# CH32V006K8U6-R0-1v0.net
KiCad netlist of a schematic drawn in Altium Designer
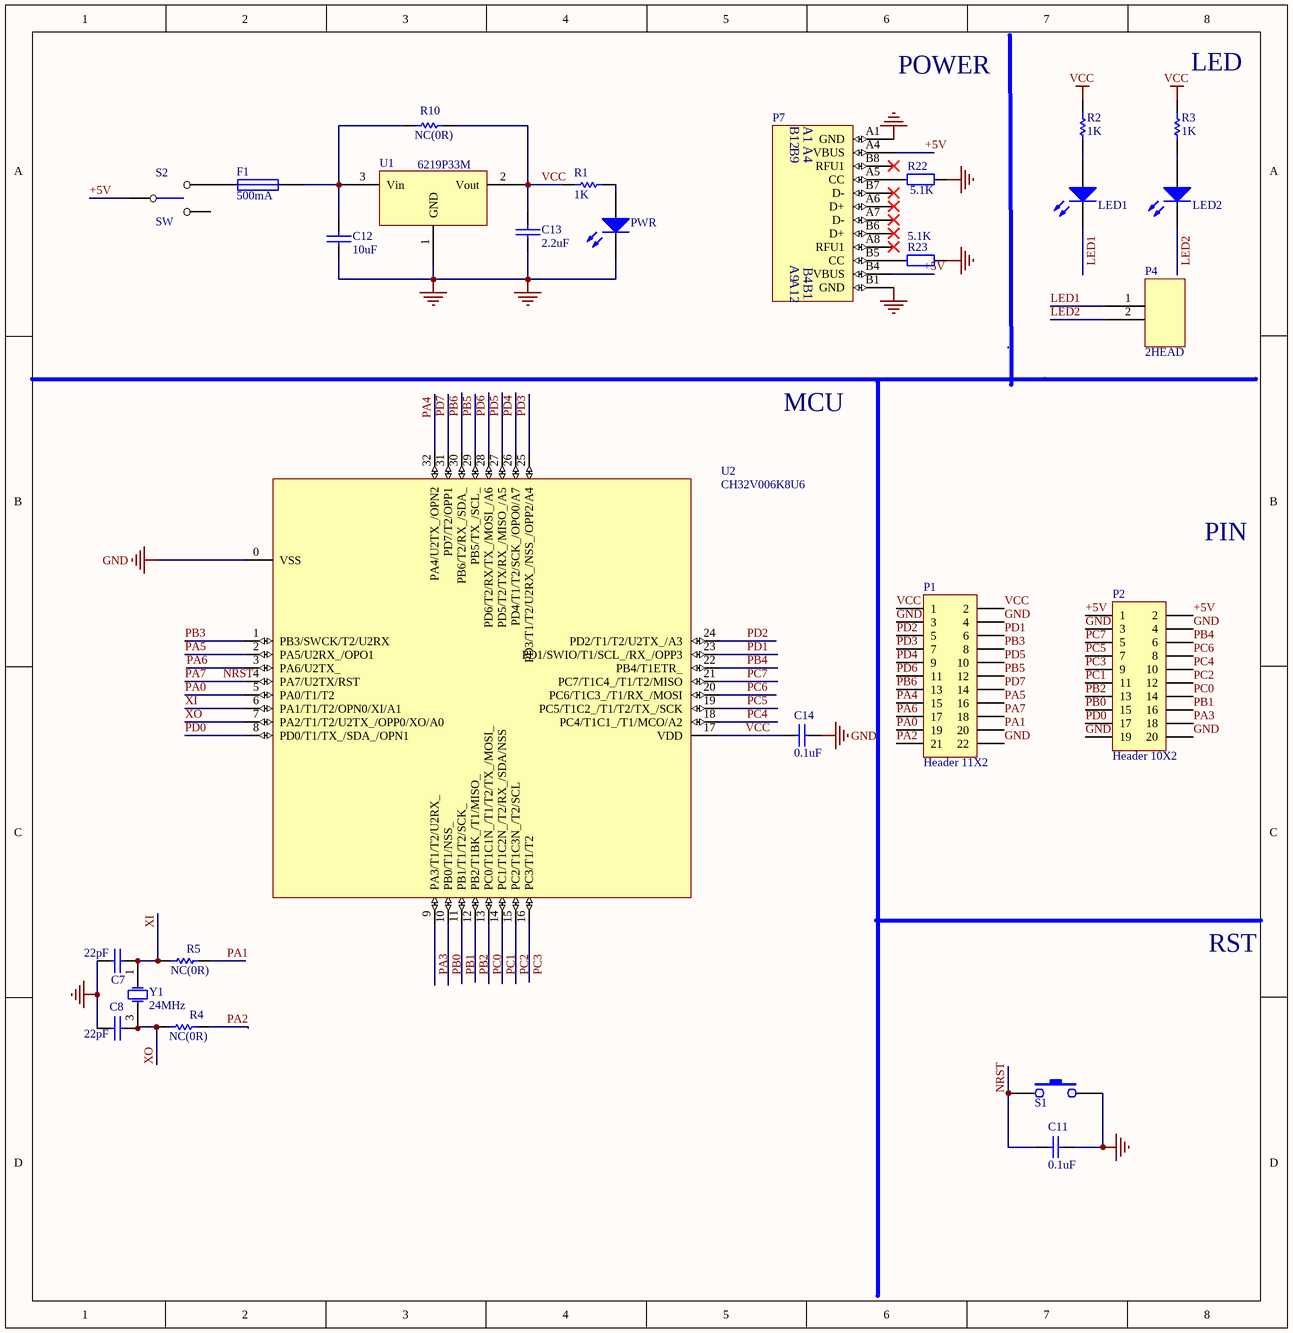
[diagram p0: CH32V006K8U6-R0-1v0.SchDoc]

(export (version "E")
  (design (tool "Eeschema 10.0.6"))
  (components
    (comp (ref "C7")
      (value "22pF")
      (footprint "0402_C")
      (description "Capacitor")
      (libsource (lib "*") (part "CAP"))
    )
    (comp (ref "C8")
      (value "22pF")
      (footprint "0402_C")
      (description "Capacitor")
      (libsource (lib "*") (part "CAP"))
    )
    (comp (ref "C11")
      (value "0.1uF")
      (footprint "0402_C")
      (description "Capacitor")
      (fields (field (name "PUBLISHER") "Altium Limited"))
      (libsource (lib "*") (part "Cap"))
    )
    (comp (ref "C12")
      (value "10uF")
      (footprint "0603_C")
      (description "Capacitor")
      (libsource (lib "wch_sch_others") (part "CAP"))
    )
    (comp (ref "C13")
      (value "2.2uF")
      (footprint "0402_C")
      (description "Capacitor")
      (libsource (lib "wch_sch_others") (part "CAP"))
    )
    (comp (ref "C14")
      (value "0.1uF")
      (footprint "0402_C")
      (description "Capacitor")
      (fields (field (name "PUBLISHER") "Altium Limited"))
      (libsource (lib "*") (part "Cap"))
    )
    (comp (ref "F1")
      (value "500mA")
      (footprint "0603")
      (description "Fuse")
      (libsource (lib "*") (part "FUSE1"))
    )
    (comp (ref "LED1")
      (value "LED1   blue")
      (footprint "0603+")
      (description "Typical INFRARED GaAs LED")
      (fields (field (name "PUBLISHER") "Altium Limited"))
      (libsource (lib "*") (part "LED0"))
    )
    (comp (ref "LED2")
      (value "LED2  blue")
      (footprint "0603+")
      (description "Typical INFRARED GaAs LED")
      (fields (field (name "PUBLISHER") "Altium Limited"))
      (libsource (lib "*") (part "LED0"))
    )
    (comp (ref "P1")
      (value "Header 11X2")
      (footprint "IDC22-2.54mm")
      (description "Header, 11-Pin, Dual row")
      (fields (field (name "PUBLISHER") "Altium Limited"))
      (libsource (lib "Miscellaneous Connectors") (part "Header 11X2"))
    )
    (comp (ref "P2")
      (value "Header 10X2")
      (footprint "IDC20-2.54mm")
      (description "Header, 10-Pin, Dual row")
      (fields (field (name "PUBLISHER") "Altium Limited"))
      (libsource (lib "Miscellaneous Connectors") (part "Header 10X2"))
    )
    (comp (ref "P4") (value "2HEAD") (footprint "SIP2-2.54mm") (libsource (lib "*") (part "2HEAD")))
    (comp (ref "P7")
      (value "TYPE-C")
      (footprint "TYPE-C-Receptacle-2.0")
      (libsource (lib "*") (part "TYPE-C1"))
    )
    (comp (ref "PWR")
      (value "POWER  red")
      (footprint "0603+")
      (description "Typical INFRARED GaAs LED")
      (fields (field (name "PUBLISHER") "Altium Limited"))
      (libsource (lib "") (part "LED0_1"))
    )
    (comp (ref "R1")
      (value "1K")
      (footprint "0402")
      (description "Semiconductor Resistor")
      (fields (field (name "PUBLISHER") "Altium Limited"))
      (libsource (lib "*") (part "Res Semi"))
    )
    (comp (ref "R2")
      (value "1K")
      (footprint "0402")
      (description "Semiconductor Resistor")
      (fields (field (name "PUBLISHER") "Altium Limited"))
      (libsource (lib "*") (part "Res Semi"))
    )
    (comp (ref "R3")
      (value "1K")
      (footprint "0402")
      (description "Semiconductor Resistor")
      (fields (field (name "PUBLISHER") "Altium Limited"))
      (libsource (lib "*") (part "Res Semi"))
    )
    (comp (ref "R4")
      (value "NC(0R)")
      (footprint "0402")
      (description "Semiconductor Resistor")
      (fields (field (name "Comment") "0R") (field (name "PUBLISHER") "Altium Limited"))
      (libsource (lib "*") (part "Res Semi"))
    )
    (comp (ref "R5")
      (value "NC(0R)")
      (footprint "0402")
      (description "Semiconductor Resistor")
      (fields (field (name "Comment") "0R") (field (name "PUBLISHER") "Altium Limited"))
      (libsource (lib "*") (part "Res Semi"))
    )
    (comp (ref "R10")
      (value "NC(0R)")
      (footprint "0402")
      (description "Semiconductor Resistor")
      (fields (field (name "Comment") "0R") (field (name "PUBLISHER") "Altium Limited"))
      (libsource (lib "*") (part "Res Semi"))
    )
    (comp (ref "R22")
      (value "5.1K")
      (footprint "0402")
      (description "Resistor")
      (libsource (lib "Miscellaneous Devices") (part "Res2"))
    )
    (comp (ref "R23")
      (value "5.1K")
      (footprint "0402")
      (description "Resistor")
      (libsource (lib "Miscellaneous Devices") (part "Res2"))
    )
    (comp (ref "S1") (value "NRST") (footprint "SMD_6.1x3.65x2.5mm-KEY") (libsource (lib "*") (part "KEY")))
    (comp (ref "S2") (value "SW") (footprint "SW1") (libsource (lib "*") (part "SW")))
    (comp (ref "U1")
      (value "6219P33M")
      (footprint "SOT-23")
      (libsource (lib "wch_sch_others") (part "6219P33M"))
    )
    (comp (ref "U2")
      (value "CH32V006K8U6")
      (footprint "QFN32_4X4")
      (description "RISC-V MCU, 48MHz, ADC/OPA/2*UART/I2C/SPI")
      (libsource (lib "CHXXX(2)") (part "CH32V006K8U6"))
    )
    (comp (ref "Y1")
      (value "24MHz")
      (footprint "XT3225")
      (description "Crystal Oscillator")
      (fields (field (name "PUBLISHER") "Altium Limited"))
      (libsource (lib "*") (part "XTAL"))
    )
  )
  (nets
    (net (code "1") (name "/+5V") (class "Default")
      (node (ref "P2") (pin "1") (pinfunction "1_1") (pintype "passive"))
      (node (ref "P2") (pin "2") (pinfunction "2_2") (pintype "passive"))
      (node (ref "P7") (pin "A4") (pinfunction "VBUS_A4") (pintype "bidirectional"))
      (node (ref "P7") (pin "B4") (pinfunction "VBUS_B4") (pintype "bidirectional"))
      (node (ref "S2") (pin "1") (pinfunction "1_1") (pintype "passive"))
    )
    (net (code "2") (name "/LED1") (class "Default")
      (node (ref "LED1") (pin "2") (pinfunction "K_2") (pintype "passive"))
      (node (ref "P4") (pin "1") (pintype "passive"))
    )
    (net (code "3") (name "/LED2") (class "Default")
      (node (ref "LED2") (pin "2") (pinfunction "K_2") (pintype "passive"))
      (node (ref "P4") (pin "2") (pintype "passive"))
    )
    (net (code "4") (name "/NRST") (class "Default")
      (node (ref "C11") (pin "2") (pinfunction "2_2") (pintype "passive"))
      (node (ref "P1") (pin "18") (pinfunction "18_18") (pintype "passive"))
      (node (ref "S1") (pin "1") (pinfunction "1_1") (pintype "passive"))
      (node (ref "U2") (pin "4") (pinfunction "PA7/U2TX/RST_4") (pintype "bidirectional"))
    )
    (net (code "5") (name "/PA0") (class "Default")
      (node (ref "P1") (pin "19") (pinfunction "19_19") (pintype "passive"))
      (node (ref "U2") (pin "5") (pinfunction "PA0/T1/T2_5") (pintype "bidirectional"))
    )
    (net (code "6") (name "/PA1") (class "Default")
      (node (ref "P1") (pin "20") (pinfunction "20_20") (pintype "passive"))
      (node (ref "R5") (pin "2") (pinfunction "2_2") (pintype "passive"))
    )
    (net (code "7") (name "/PA2") (class "Default")
      (node (ref "P1") (pin "21") (pinfunction "21_21") (pintype "passive"))
      (node (ref "R4") (pin "2") (pinfunction "2_2") (pintype "passive"))
    )
    (net (code "8") (name "/PA3") (class "Default")
      (node (ref "P2") (pin "18") (pinfunction "18_18") (pintype "passive"))
      (node (ref "U2") (pin "9") (pinfunction "PA3/T1/T2/U2RX__9") (pintype "bidirectional"))
    )
    (net (code "9") (name "/PA4") (class "Default")
      (node (ref "P1") (pin "15") (pinfunction "15_15") (pintype "passive"))
      (node (ref "U2") (pin "32") (pinfunction "PA4/U2TX_/OPN2_32") (pintype "bidirectional"))
    )
    (net (code "10") (name "/PA5") (class "Default")
      (node (ref "P1") (pin "16") (pinfunction "16_16") (pintype "passive"))
      (node (ref "U2") (pin "2") (pinfunction "PA5/U2RX_/OPO1_2") (pintype "bidirectional"))
    )
    (net (code "11") (name "/PA6") (class "Default")
      (node (ref "P1") (pin "17") (pinfunction "17_17") (pintype "passive"))
      (node (ref "U2") (pin "3") (pinfunction "PA6/U2TX__3") (pintype "bidirectional"))
    )
    (net (code "12") (name "/PB0") (class "Default")
      (node (ref "P2") (pin "15") (pinfunction "15_15") (pintype "passive"))
      (node (ref "U2") (pin "10") (pinfunction "PB0/T1/NSS__10") (pintype "bidirectional"))
    )
    (net (code "13") (name "/PB1") (class "Default")
      (node (ref "P2") (pin "16") (pinfunction "16_16") (pintype "passive"))
      (node (ref "U2") (pin "11") (pinfunction "PB1/T1/T2/SCK__11") (pintype "bidirectional"))
    )
    (net (code "14") (name "/PB2") (class "Default")
      (node (ref "P2") (pin "13") (pinfunction "13_13") (pintype "passive"))
      (node (ref "U2") (pin "12") (pinfunction "PB2/T1BK_/T1/MISO__12") (pintype "bidirectional"))
    )
    (net (code "15") (name "/PB3") (class "Default")
      (node (ref "P1") (pin "8") (pinfunction "8_8") (pintype "passive"))
      (node (ref "U2") (pin "1") (pinfunction "PB3/SWCK/T2/U2RX_1") (pintype "bidirectional"))
    )
    (net (code "16") (name "/PB4") (class "Default")
      (node (ref "P2") (pin "6") (pinfunction "6_6") (pintype "passive"))
      (node (ref "U2") (pin "22") (pinfunction "PB4/T1ETR__22") (pintype "bidirectional"))
    )
    (net (code "17") (name "/PB5") (class "Default")
      (node (ref "P1") (pin "12") (pinfunction "12_12") (pintype "passive"))
      (node (ref "U2") (pin "29") (pinfunction "PB5/TX_/SCL__29") (pintype "bidirectional"))
    )
    (net (code "18") (name "/PB6") (class "Default")
      (node (ref "P1") (pin "13") (pinfunction "13_13") (pintype "passive"))
      (node (ref "U2") (pin "30") (pinfunction "PB6/T2/RX_/SDA__30") (pintype "bidirectional"))
    )
    (net (code "19") (name "/PC0") (class "Default")
      (node (ref "P2") (pin "14") (pinfunction "14_14") (pintype "passive"))
      (node (ref "U2") (pin "13") (pinfunction "PC0/T1C1N_/T1/T2/TX_/MOSI__13") (pintype "bidirectional"))
    )
    (net (code "20") (name "/PC1") (class "Default")
      (node (ref "P2") (pin "11") (pinfunction "11_11") (pintype "passive"))
      (node (ref "U2") (pin "14") (pinfunction "PC1/T1C2N_/T2/RX_/SDA/NSS_14") (pintype "bidirectional"))
    )
    (net (code "21") (name "/PC2") (class "Default")
      (node (ref "P2") (pin "12") (pinfunction "12_12") (pintype "passive"))
      (node (ref "U2") (pin "15") (pinfunction "PC2/T1C3N_/T2/SCL_15") (pintype "bidirectional"))
    )
    (net (code "22") (name "/PC3") (class "Default")
      (node (ref "P2") (pin "9") (pinfunction "9_9") (pintype "passive"))
      (node (ref "U2") (pin "16") (pinfunction "PC3/T1/T2_16") (pintype "bidirectional"))
    )
    (net (code "23") (name "/PC4") (class "Default")
      (node (ref "P2") (pin "10") (pinfunction "10_10") (pintype "passive"))
      (node (ref "U2") (pin "18") (pinfunction "PC4/T1C1_/T1/MCO/A2_18") (pintype "bidirectional"))
    )
    (net (code "24") (name "/PC5") (class "Default")
      (node (ref "P2") (pin "7") (pinfunction "7_7") (pintype "passive"))
      (node (ref "U2") (pin "19") (pinfunction "PC5/T1C2_/T1/T2/TX_/SCK_19") (pintype "bidirectional"))
    )
    (net (code "25") (name "/PC6") (class "Default")
      (node (ref "P2") (pin "8") (pinfunction "8_8") (pintype "passive"))
      (node (ref "U2") (pin "20") (pinfunction "PC6/T1C3_/T1/RX_/MOSI_20") (pintype "bidirectional"))
    )
    (net (code "26") (name "/PC7") (class "Default")
      (node (ref "P2") (pin "5") (pinfunction "5_5") (pintype "passive"))
      (node (ref "U2") (pin "21") (pinfunction "PC7/T1C4_/T1/T2/MISO_21") (pintype "bidirectional"))
    )
    (net (code "27") (name "/PD0") (class "Default")
      (node (ref "P2") (pin "17") (pinfunction "17_17") (pintype "passive"))
      (node (ref "U2") (pin "8") (pinfunction "PD0/T1/TX_/SDA_/OPN1_8") (pintype "bidirectional"))
    )
    (net (code "28") (name "/PD1") (class "Default")
      (node (ref "P1") (pin "6") (pinfunction "6_6") (pintype "passive"))
      (node (ref "U2") (pin "23") (pinfunction "PD1/SWIO/T1/SCL_/RX_/OPP3_23") (pintype "bidirectional"))
    )
    (net (code "29") (name "/PD2") (class "Default")
      (node (ref "P1") (pin "5") (pinfunction "5_5") (pintype "passive"))
      (node (ref "U2") (pin "24") (pinfunction "PD2/T1/T2/U2TX_/A3_24") (pintype "bidirectional"))
    )
    (net (code "30") (name "/PD3") (class "Default")
      (node (ref "P1") (pin "7") (pinfunction "7_7") (pintype "passive"))
      (node (ref "U2") (pin "25") (pinfunction "PD3/T1/T2/U2RX_/NSS_/OPP2/A4_25") (pintype "bidirectional"))
    )
    (net (code "31") (name "/PD4") (class "Default")
      (node (ref "P1") (pin "9") (pinfunction "9_9") (pintype "passive"))
      (node (ref "U2") (pin "26") (pinfunction "PD4/T1/T2/SCK_/OPO0/A7_26") (pintype "bidirectional"))
    )
    (net (code "32") (name "/PD5") (class "Default")
      (node (ref "P1") (pin "10") (pinfunction "10_10") (pintype "passive"))
      (node (ref "U2") (pin "27") (pinfunction "PD5/T2/TX/RX_/MISO_/A5_27") (pintype "bidirectional"))
    )
    (net (code "33") (name "/PD6") (class "Default")
      (node (ref "P1") (pin "11") (pinfunction "11_11") (pintype "passive"))
      (node (ref "U2") (pin "28") (pinfunction "PD6/T2/RX/TX_/MOSI_/A6_28") (pintype "bidirectional"))
    )
    (net (code "34") (name "/PD7") (class "Default")
      (node (ref "P1") (pin "14") (pinfunction "14_14") (pintype "passive"))
      (node (ref "U2") (pin "31") (pinfunction "PD7/T2/OPP1_31") (pintype "bidirectional"))
    )
    (net (code "35") (name "/XI") (class "Default")
      (node (ref "C7") (pin "2") (pinfunction "2_2") (pintype "passive"))
      (node (ref "R5") (pin "1") (pinfunction "1_1") (pintype "passive"))
      (node (ref "U2") (pin "6") (pinfunction "PA1/T1/T2/OPN0/XI/A1_6") (pintype "bidirectional"))
      (node (ref "Y1") (pin "1") (pinfunction "OSC1_1") (pintype "passive"))
    )
    (net (code "36") (name "/XO") (class "Default")
      (node (ref "C8") (pin "2") (pinfunction "2_2") (pintype "passive"))
      (node (ref "R4") (pin "1") (pinfunction "1_1") (pintype "passive"))
      (node (ref "U2") (pin "7") (pinfunction "PA2/T1/T2/U2TX_/OPP0/XO/A0_7") (pintype "bidirectional"))
      (node (ref "Y1") (pin "3") (pinfunction "OSC2_3") (pintype "passive"))
    )
    (net (code "37") (name "GND") (class "Default")
      (node (ref "C11") (pin "1") (pinfunction "1_1") (pintype "passive"))
      (node (ref "C12") (pin "2") (pinfunction "2_2") (pintype "passive"))
      (node (ref "C13") (pin "1") (pinfunction "1_1") (pintype "passive"))
      (node (ref "C14") (pin "2") (pinfunction "2_2") (pintype "passive"))
      (node (ref "C7") (pin "1") (pinfunction "1_1") (pintype "passive"))
      (node (ref "C8") (pin "1") (pinfunction "1_1") (pintype "passive"))
      (node (ref "P1") (pin "22") (pinfunction "22_22") (pintype "passive"))
      (node (ref "P1") (pin "3") (pinfunction "3_3") (pintype "passive"))
      (node (ref "P1") (pin "4") (pinfunction "4_4") (pintype "passive"))
      (node (ref "P2") (pin "19") (pinfunction "19_19") (pintype "passive"))
      (node (ref "P2") (pin "20") (pinfunction "20_20") (pintype "passive"))
      (node (ref "P2") (pin "3") (pinfunction "3_3") (pintype "passive"))
      (node (ref "P2") (pin "4") (pinfunction "4_4") (pintype "passive"))
      (node (ref "P7") (pin "A1") (pinfunction "GND_A1") (pintype "bidirectional"))
      (node (ref "P7") (pin "B1") (pinfunction "GND_B1") (pintype "bidirectional"))
      (node (ref "PWR") (pin "2") (pinfunction "K_2") (pintype "passive"))
      (node (ref "R22") (pin "2") (pinfunction "2_2") (pintype "passive"))
      (node (ref "R23") (pin "2") (pinfunction "2_2") (pintype "passive"))
      (node (ref "S1") (pin "2") (pinfunction "2_2") (pintype "passive"))
      (node (ref "U1") (pin "1") (pinfunction "GND_1") (pintype "passive"))
      (node (ref "U2") (pin "0") (pinfunction "VSS_0") (pintype "power_in"))
    )
    (net (code "38") (name "Net-(F1-Pad1)") (class "Default")
      (node (ref "F1") (pin "1") (pinfunction "1_1") (pintype "passive"))
      (node (ref "S2") (pin "3") (pinfunction "3_3") (pintype "passive"))
    )
    (net (code "39") (name "Net-(LED1-A)") (class "Default")
      (node (ref "LED1") (pin "1") (pinfunction "A_1") (pintype "passive"))
      (node (ref "R2") (pin "2") (pinfunction "2_2") (pintype "passive"))
    )
    (net (code "40") (name "Net-(LED2-A)") (class "Default")
      (node (ref "LED2") (pin "1") (pinfunction "A_1") (pintype "passive"))
      (node (ref "R3") (pin "2") (pinfunction "2_2") (pintype "passive"))
    )
    (net (code "41") (name "Net-(P7-CC-PadA5)") (class "Default")
      (node (ref "P7") (pin "A5") (pinfunction "CC_A5") (pintype "bidirectional"))
      (node (ref "R22") (pin "1") (pinfunction "1_1") (pintype "passive"))
    )
    (net (code "42") (name "Net-(P7-CC-PadB5)") (class "Default")
      (node (ref "P7") (pin "B5") (pinfunction "CC_B5") (pintype "bidirectional"))
      (node (ref "R23") (pin "1") (pinfunction "1_1") (pintype "passive"))
    )
    (net (code "43") (name "Net-(PWR-A)") (class "Default")
      (node (ref "PWR") (pin "1") (pinfunction "A_1") (pintype "passive"))
      (node (ref "R1") (pin "1") (pinfunction "1_1") (pintype "passive"))
    )
    (net (code "44") (name "Net-(U1-Vin)") (class "Default")
      (node (ref "C12") (pin "1") (pinfunction "1_1") (pintype "passive"))
      (node (ref "F1") (pin "2") (pinfunction "2_2") (pintype "passive"))
      (node (ref "R10") (pin "1") (pinfunction "1_1") (pintype "passive"))
      (node (ref "U1") (pin "3") (pinfunction "Vin_3") (pintype "passive"))
    )
    (net (code "45") (name "VCC") (class "Default")
      (node (ref "C13") (pin "2") (pinfunction "2_2") (pintype "passive"))
      (node (ref "C14") (pin "1") (pinfunction "1_1") (pintype "passive"))
      (node (ref "P1") (pin "1") (pinfunction "1_1") (pintype "passive"))
      (node (ref "P1") (pin "2") (pinfunction "2_2") (pintype "passive"))
      (node (ref "R1") (pin "2") (pinfunction "2_2") (pintype "passive"))
      (node (ref "R10") (pin "2") (pinfunction "2_2") (pintype "passive"))
      (node (ref "R2") (pin "1") (pinfunction "1_1") (pintype "passive"))
      (node (ref "R3") (pin "1") (pinfunction "1_1") (pintype "passive"))
      (node (ref "U1") (pin "2") (pinfunction "Vout_2") (pintype "passive"))
      (node (ref "U2") (pin "17") (pinfunction "VDD_17") (pintype "power_in"))
    )
    (net (code "46") (name "unconnected-(P7-D+-PadA6)") (class "Default")
      (node (ref "P7") (pin "A6") (pinfunction "D+_A6") (pintype "bidirectional+no_connect"))
    )
    (net (code "47") (name "unconnected-(P7-D+-PadB6)") (class "Default")
      (node (ref "P7") (pin "B6") (pinfunction "D+_B6") (pintype "bidirectional+no_connect"))
    )
    (net (code "48") (name "unconnected-(P7-D--PadA7)") (class "Default")
      (node (ref "P7") (pin "A7") (pinfunction "D-_A7") (pintype "bidirectional+no_connect"))
    )
    (net (code "49") (name "unconnected-(P7-D--PadB7)") (class "Default")
      (node (ref "P7") (pin "B7") (pinfunction "D-_B7") (pintype "bidirectional+no_connect"))
    )
    (net (code "50") (name "unconnected-(P7-RFU1-PadA8)") (class "Default")
      (node (ref "P7") (pin "A8") (pinfunction "RFU1_A8") (pintype "bidirectional+no_connect"))
    )
    (net (code "51") (name "unconnected-(P7-RFU1-PadB8)") (class "Default")
      (node (ref "P7") (pin "B8") (pinfunction "RFU1_B8") (pintype "bidirectional+no_connect"))
    )
    (net (code "52") (name "unconnected-(S2-Pad2)") (class "Default")
      (node (ref "S2") (pin "2") (pinfunction "2_2") (pintype "passive"))
    )
  )
)
